# Gyroscope.net
KiCad netlist of a schematic drawn in Altium Designer
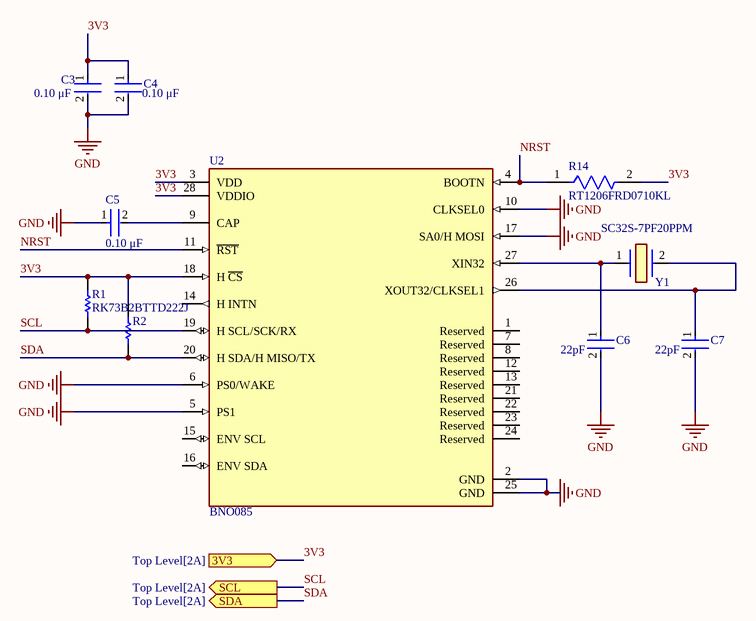
[diagram p0: Gyroscope.SchDoc]

(export (version "E")
  (design (tool "Eeschema 10.0.6"))
  (components
    (comp (ref "C3")
      (value "C1206C104M5RACTU")
      (footprint "FP-C1206C-EB-MFG")
      (description "CAP CER 0.1UF 50V X7R 1206")
      (fields
        (field (name "OCTOPART") "https://octopart.com/c1206c104m5ractu-kemet-129344")
        (field (name "TOLERANCE") "0.2")
        (field (name "CAPACITANCE") "0.10 μF")
      )
      (libsource (lib "Altium Content Vault") (part "b4654b650e69147ec39a6b967a45e02"))
    )
    (comp (ref "C4")
      (value "C1206C104M5RACTU")
      (footprint "FP-C1206C-EB-MFG")
      (description "CAP CER 0.1UF 50V X7R 1206")
      (fields
        (field (name "OCTOPART") "https://octopart.com/c1206c104m5ractu-kemet-129344")
        (field (name "TOLERANCE") "0.2")
        (field (name "CAPACITANCE") "0.10 μF")
      )
      (libsource (lib "Altium Content Vault") (part "b4654b650e69147ec39a6b967a45e02"))
    )
    (comp (ref "C5")
      (value "C1206C104M5RACTU")
      (footprint "FP-C1206C-EB-MFG")
      (description "CAP CER 0.1UF 50V X7R 1206")
      (fields
        (field (name "OCTOPART") "https://octopart.com/c1206c104m5ractu-kemet-129344")
        (field (name "TOLERANCE") "0.2")
        (field (name "CAPACITANCE") "0.10 μF")
      )
      (libsource (lib "Altium Content Vault") (part "b4654b650e69147ec39a6b967a45e02"))
    )
    (comp (ref "C6")
      (value "CL31C220JBCNNNC")
      (footprint "FP-CL31-IPC_A")
      (description "Cap Ceramic 22pF 50V C0G ±5% SMD 1206 +125°C Embossed T/R")
      (fields
        (field (name "VOLTAGE") "50V")
        (field (name "TOLERANCE") "5%")
        (field (name "CAPACITANCE") "22pF")
      )
      (libsource (lib "Altium Content Vault") (part "b4654b650e69147ec39a6b967a45e02"))
    )
    (comp (ref "C7")
      (value "CL31C220JBCNNNC")
      (footprint "FP-CL31-IPC_A")
      (description "Cap Ceramic 22pF 50V C0G ±5% SMD 1206 +125°C Embossed T/R")
      (fields
        (field (name "VOLTAGE") "50V")
        (field (name "TOLERANCE") "5%")
        (field (name "CAPACITANCE") "22pF")
      )
      (libsource (lib "Altium Content Vault") (part "b4654b650e69147ec39a6b967a45e02"))
    )
    (comp (ref "R1")
      (value "RK73B2BTTD222J")
      (footprint "RESC3216X70X40LL20T20")
      (fields (field (name "MANUFACTURER") "KOA Speer"))
      (libsource (lib "Altium Content Vault") (part "RES"))
    )
    (comp (ref "R2")
      (value "RK73B2BTTD222J")
      (footprint "RESC3216X70X40LL20T20")
      (fields (field (name "MANUFACTURER") "KOA Speer"))
      (libsource (lib "Altium Content Vault") (part "RES"))
    )
    (comp (ref "R14")
      (value "RT1206FRD0710KL")
      (footprint "FP-RT1206-MFG")
      (description "RT1206 10KΩ 0.25W 25 ppm/°C 0.02%")
      (fields (field (name "MANUFACTURER") "Yageo"))
      (libsource (lib "Altium Content Vault") (part "1029c3af85768c4190bb7ad29bc67b5"))
    )
    (comp (ref "U2")
      (value "BNO085")
      (footprint "FP-BNO085-MFG")
      (description "IMU ACCEL/GYRO/MAG I2C 32BIT")
      (libsource (lib "Jason Zhou") (part "87552c951d161a888c2c69b58ce40bc"))
    )
    (comp (ref "Y1")
      (value "SC32S-7PF20PPM")
      (footprint "SamacSys:SC32S7PF20PPM")
      (description "Crystal or Oscillator")
      (fields (field (name "MOUSER PART NUMBER") "628-SC32S-7PF20PPM"))
      (libsource (lib "*") (part "SC32S-7PF20PPM"))
    )
  )
  (nets
    (net (code "1") (name "/3V3") (class "Default")
      (node (ref "C3") (pin "1") (pinfunction "1_1") (pintype "passive"))
      (node (ref "C4") (pin "1") (pinfunction "1_1") (pintype "passive"))
      (node (ref "R1") (pin "2") (pinfunction "2_2") (pintype "passive"))
      (node (ref "R14") (pin "2") (pinfunction "2_2") (pintype "passive"))
      (node (ref "R2") (pin "2") (pinfunction "2_2") (pintype "passive"))
      (node (ref "U2") (pin "18") (pinfunction "H_~{CS}_18") (pintype "input"))
      (node (ref "U2") (pin "28") (pinfunction "VDDIO_28") (pintype "passive"))
      (node (ref "U2") (pin "3") (pinfunction "VDD_3") (pintype "passive"))
    )
    (net (code "2") (name "/NRST") (class "Default")
      (node (ref "R14") (pin "1") (pinfunction "1_1") (pintype "passive"))
      (node (ref "U2") (pin "11") (pinfunction "~{RST}_11") (pintype "input"))
      (node (ref "U2") (pin "4") (pinfunction "BOOTN_4") (pintype "input"))
    )
    (net (code "3") (name "/SCL") (class "Default")
      (node (ref "R1") (pin "1") (pinfunction "1_1") (pintype "passive"))
      (node (ref "U2") (pin "19") (pinfunction "H_SCL/SCK/RX_19") (pintype "bidirectional"))
    )
    (net (code "4") (name "/SDA") (class "Default")
      (node (ref "R2") (pin "1") (pinfunction "1_1") (pintype "passive"))
      (node (ref "U2") (pin "20") (pinfunction "H_SDA/H_MISO/TX_20") (pintype "bidirectional"))
    )
    (net (code "5") (name "GND") (class "Default")
      (node (ref "C3") (pin "2") (pinfunction "2_2") (pintype "passive"))
      (node (ref "C4") (pin "2") (pinfunction "2_2") (pintype "passive"))
      (node (ref "C5") (pin "1") (pinfunction "1_1") (pintype "passive"))
      (node (ref "C6") (pin "2") (pinfunction "2_2") (pintype "passive"))
      (node (ref "C7") (pin "2") (pinfunction "2_2") (pintype "passive"))
      (node (ref "U2") (pin "10") (pinfunction "CLKSEL0_10") (pintype "input"))
      (node (ref "U2") (pin "17") (pinfunction "SA0/H_MOSI_17") (pintype "input"))
      (node (ref "U2") (pin "2") (pinfunction "GND_2") (pintype "passive"))
      (node (ref "U2") (pin "25") (pinfunction "GND_25") (pintype "passive"))
      (node (ref "U2") (pin "5") (pinfunction "PS1_5") (pintype "input"))
      (node (ref "U2") (pin "6") (pinfunction "PS0/WAKE_6") (pintype "input"))
    )
    (net (code "6") (name "Net-(U2-CAP)") (class "Default")
      (node (ref "C5") (pin "2") (pinfunction "2_2") (pintype "passive"))
      (node (ref "U2") (pin "9") (pinfunction "CAP_9") (pintype "passive"))
    )
    (net (code "7") (name "Net-(U2-XIN32)") (class "Default")
      (node (ref "C6") (pin "1") (pinfunction "1_1") (pintype "passive"))
      (node (ref "U2") (pin "27") (pinfunction "XIN32_27") (pintype "input"))
      (node (ref "Y1") (pin "1") (pinfunction "1_1") (pintype "passive"))
    )
    (net (code "8") (name "Net-(U2-XOUT32{slash}CLKSEL1)") (class "Default")
      (node (ref "C7") (pin "1") (pinfunction "1_1") (pintype "passive"))
      (node (ref "U2") (pin "26") (pinfunction "XOUT32/CLKSEL1_26") (pintype "output"))
      (node (ref "Y1") (pin "2") (pinfunction "2_2") (pintype "passive"))
    )
    (net (code "9") (name "unconnected-(U2-ENV_SCL-Pad15)") (class "Default")
      (node (ref "U2") (pin "15") (pinfunction "ENV_SCL_15") (pintype "bidirectional"))
    )
    (net (code "10") (name "unconnected-(U2-ENV_SDA-Pad16)") (class "Default")
      (node (ref "U2") (pin "16") (pinfunction "ENV_SDA_16") (pintype "bidirectional"))
    )
    (net (code "11") (name "unconnected-(U2-H_INTN-Pad14)") (class "Default")
      (node (ref "U2") (pin "14") (pinfunction "H_INTN_14") (pintype "output"))
    )
    (net (code "12") (name "unconnected-(U2-Reserved-Pad1)") (class "Default")
      (node (ref "U2") (pin "1") (pinfunction "Reserved_1") (pintype "passive"))
    )
    (net (code "13") (name "unconnected-(U2-Reserved-Pad7)") (class "Default")
      (node (ref "U2") (pin "7") (pinfunction "Reserved_7") (pintype "passive"))
    )
    (net (code "14") (name "unconnected-(U2-Reserved-Pad8)") (class "Default")
      (node (ref "U2") (pin "8") (pinfunction "Reserved_8") (pintype "passive"))
    )
    (net (code "15") (name "unconnected-(U2-Reserved-Pad12)") (class "Default")
      (node (ref "U2") (pin "12") (pinfunction "Reserved_12") (pintype "passive"))
    )
    (net (code "16") (name "unconnected-(U2-Reserved-Pad13)") (class "Default")
      (node (ref "U2") (pin "13") (pinfunction "Reserved_13") (pintype "passive"))
    )
    (net (code "17") (name "unconnected-(U2-Reserved-Pad21)") (class "Default")
      (node (ref "U2") (pin "21") (pinfunction "Reserved_21") (pintype "passive"))
    )
    (net (code "18") (name "unconnected-(U2-Reserved-Pad22)") (class "Default")
      (node (ref "U2") (pin "22") (pinfunction "Reserved_22") (pintype "passive"))
    )
    (net (code "19") (name "unconnected-(U2-Reserved-Pad23)") (class "Default")
      (node (ref "U2") (pin "23") (pinfunction "Reserved_23") (pintype "passive"))
    )
    (net (code "20") (name "unconnected-(U2-Reserved-Pad24)") (class "Default")
      (node (ref "U2") (pin "24") (pinfunction "Reserved_24") (pintype "passive"))
    )
  )
)
